# Arduino_MINI.net
KiCad netlist of a schematic drawn in Altium Designer
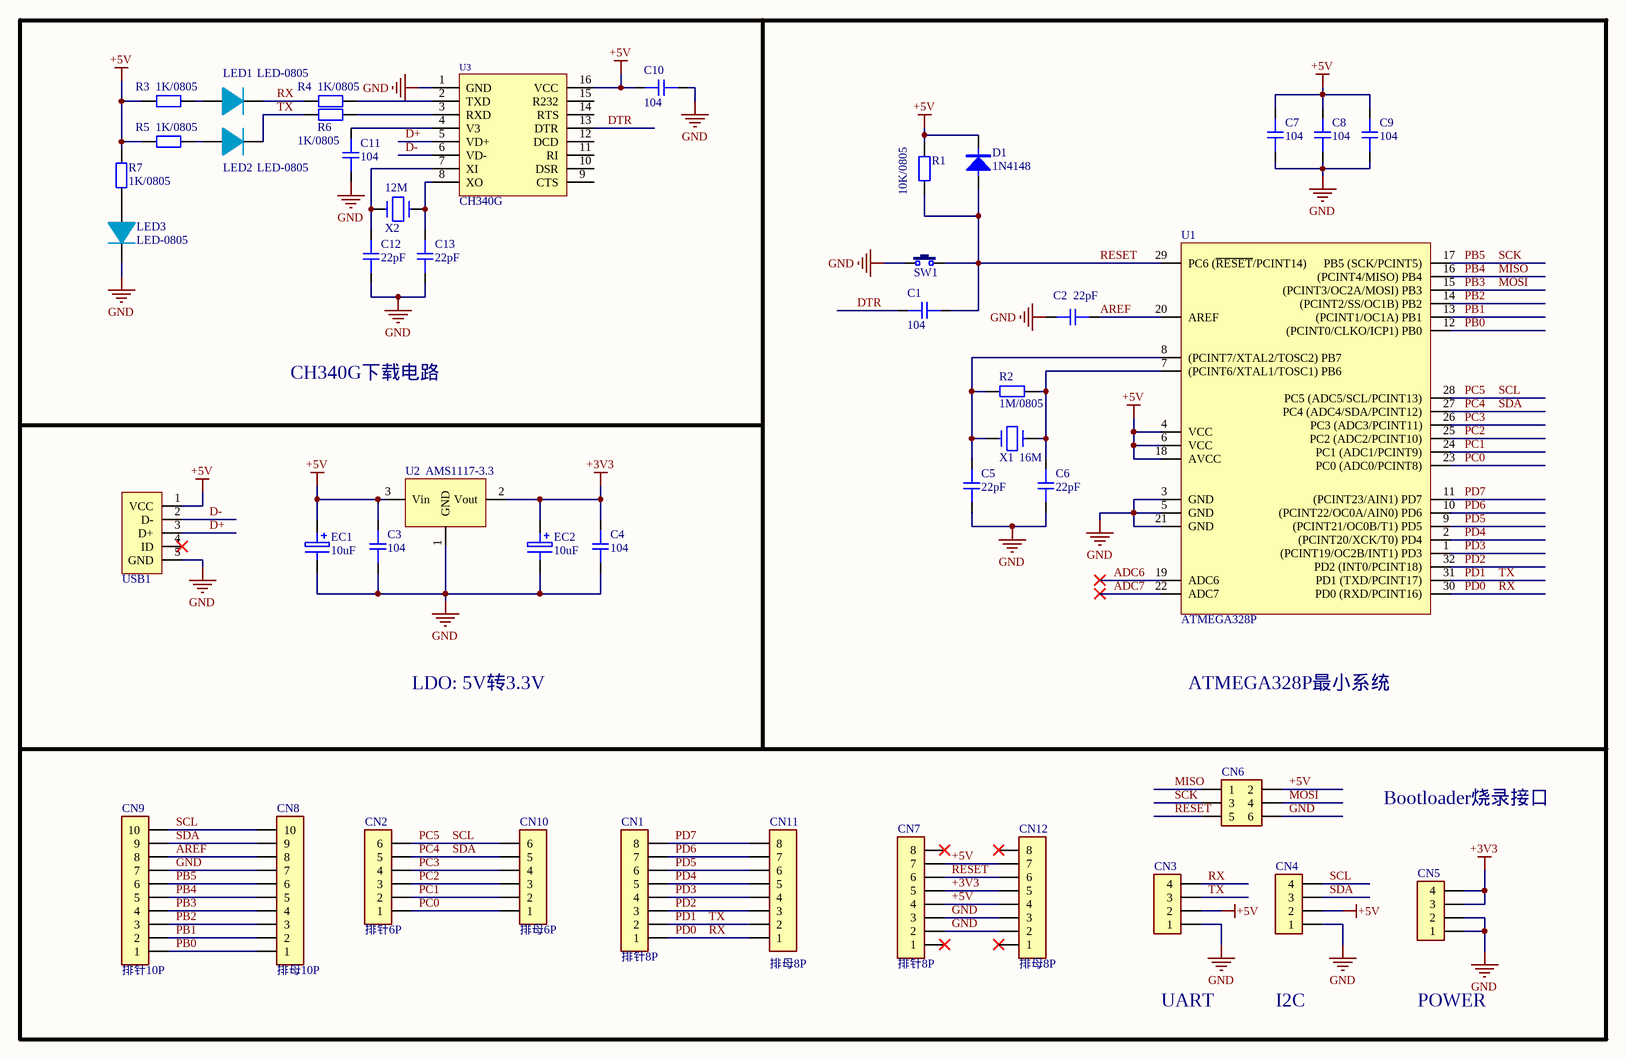
[diagram p0: Arduino开发板 MINI款.SchDoc]

(export (version "E")
  (design (tool "Eeschema 10.0.6"))
  (components
    (comp (ref "C1")
      (value "104")
      (footprint "C0805-SMT")
      (description "C")
      (libsource (lib "新-MZ-Library 2018-1-10") (part "C"))
    )
    (comp (ref "C2")
      (value "22pF")
      (footprint "C0805-SMT")
      (description "C")
      (libsource (lib "新-MZ-Library 2018-1-10") (part "C"))
    )
    (comp (ref "C3")
      (value "104")
      (footprint "C0805-SMT")
      (description "C")
      (libsource (lib "新-MZ-Library 2018-1-10") (part "C"))
    )
    (comp (ref "C4")
      (value "104")
      (footprint "C0805-SMT")
      (description "C")
      (libsource (lib "新-MZ-Library 2018-1-10") (part "C"))
    )
    (comp (ref "C5")
      (value "22pF")
      (footprint "C0805-SMT")
      (description "C")
      (libsource (lib "新-MZ-Library 2018-1-10") (part "C"))
    )
    (comp (ref "C6")
      (value "22pF")
      (footprint "C0805-SMT")
      (description "C")
      (libsource (lib "新-MZ-Library 2018-1-10") (part "C"))
    )
    (comp (ref "C7")
      (value "104")
      (footprint "C0805-SMT")
      (description "C")
      (libsource (lib "新-MZ-Library 2018-1-10") (part "C"))
    )
    (comp (ref "C8")
      (value "104")
      (footprint "C0805-SMT")
      (description "C")
      (libsource (lib "新-MZ-Library 2018-1-10") (part "C"))
    )
    (comp (ref "C9")
      (value "104")
      (footprint "C0805-SMT")
      (description "C")
      (libsource (lib "新-MZ-Library 2018-1-10") (part "C"))
    )
    (comp (ref "C10")
      (value "104")
      (footprint "C0805-SMT")
      (description "C")
      (libsource (lib "新-MZ-Library 2018-1-10") (part "C"))
    )
    (comp (ref "C11")
      (value "104")
      (footprint "C0805-SMT")
      (description "C")
      (libsource (lib "新-MZ-Library 2018-1-10") (part "C"))
    )
    (comp (ref "C12")
      (value "22pF")
      (footprint "C0805-SMT")
      (description "C")
      (libsource (lib "新-MZ-Library 2018-1-10") (part "C"))
    )
    (comp (ref "C13")
      (value "22pF")
      (footprint "C0805-SMT")
      (description "C")
      (libsource (lib "新-MZ-Library 2018-1-10") (part "C"))
    )
    (comp (ref "CN1")
      (value "排针8P")
      (footprint "sip8")
      (description "8P-SOCKET")
      (libsource (lib "") (part "CN8_1"))
    )
    (comp (ref "CN2")
      (value "排针6P")
      (footprint "sip6")
      (description "6P-SOCKET")
      (libsource (lib "") (part "CN6_1"))
    )
    (comp (ref "CN3")
      (value "CN4")
      (footprint "sip4")
      (description "4P-SOCKET")
      (libsource (lib "原理库MZ-Library 2021-2") (part "CN4"))
    )
    (comp (ref "CN4")
      (value "CN4")
      (footprint "sip4")
      (description "4P-SOCKET")
      (libsource (lib "原理库MZ-Library 2021-2") (part "CN4"))
    )
    (comp (ref "CN5")
      (value "CN4")
      (footprint "sip4")
      (description "4P-SOCKET")
      (libsource (lib "原理库MZ-Library 2021-2") (part "CN4"))
    )
    (comp (ref "CN6")
      (value "CN2*3")
      (footprint "sip2*3")
      (libsource (lib "原理库MZ-Library 2021-2") (part "CN2*3"))
    )
    (comp (ref "CN7")
      (value "排针8P")
      (footprint "SIP8")
      (description "8P-SOCKET")
      (libsource (lib "") (part "CN8_1"))
    )
    (comp (ref "CN8")
      (value "排母10P")
      (footprint "HDR2.54-M-LI-10P")
      (description "10P-SOCKET")
      (libsource (lib "原理库MZ-Library 2021-2") (part "CN10"))
    )
    (comp (ref "CN9")
      (value "排针10P")
      (footprint "SIP10")
      (description "10P-SOCKET")
      (libsource (lib "") (part "CN10_1"))
    )
    (comp (ref "CN10")
      (value "排母6P")
      (footprint "HDR2.54-M-LI-6P")
      (description "6P-SOCKET")
      (libsource (lib "原理库MZ-Library 2021-2") (part "CN6"))
    )
    (comp (ref "CN11")
      (value "排母8P")
      (footprint "HDR2.54-M-LI-8P")
      (description "8P-SOCKET")
      (libsource (lib "原理库MZ-Library 2021-2") (part "CN8"))
    )
    (comp (ref "CN12")
      (value "排母8P")
      (footprint "HDR2.54-M-LI-8P")
      (description "8P-SOCKET")
      (libsource (lib "原理库MZ-Library 2021-2") (part "CN8"))
    )
    (comp (ref "D1")
      (value "1N4148")
      (footprint "SOD123/F(4148)-SMT")
      (description "DIODE")
      (libsource (lib "新-MZ-Library 2018-1-10") (part "D"))
    )
    (comp (ref "EC1")
      (value "10uF")
      (footprint "CAE2.54-Φ5-AI")
      (description "EA")
      (libsource (lib "原理库MZ-Library 2021-2") (part "CAE"))
    )
    (comp (ref "EC2")
      (value "10uF")
      (footprint "CAE2.54-Φ5-AI")
      (description "EA")
      (libsource (lib "原理库MZ-Library 2021-2") (part "CAE"))
    )
    (comp (ref "LED1")
      (value "LED-0805")
      (footprint "LED 0805R")
      (description "LED_0805")
      (libsource (lib "常用元器件") (part "LED-0805"))
    )
    (comp (ref "LED2")
      (value "LED-0805")
      (footprint "LED 0805R")
      (description "LED_0805")
      (libsource (lib "常用元器件") (part "LED-0805"))
    )
    (comp (ref "LED3")
      (value "LED-0805")
      (footprint "LED 0805R")
      (description "LED_0805")
      (libsource (lib "常用元器件") (part "LED-0805"))
    )
    (comp (ref "R1")
      (value "10K/0805")
      (footprint "R0805-SMT")
      (description "RES")
      (libsource (lib "新-MZ-Library 2018-1-10") (part "R"))
    )
    (comp (ref "R2")
      (value "1M/0805")
      (footprint "R0805-SMT")
      (description "RES")
      (libsource (lib "新-MZ-Library 2018-1-10") (part "R"))
    )
    (comp (ref "R3")
      (value "1K/0805")
      (footprint "R0805-SMT")
      (description "RES")
      (libsource (lib "新-MZ-Library 2018-1-10") (part "R"))
    )
    (comp (ref "R4")
      (value "1K/0805")
      (footprint "R0805-SMT")
      (description "RES")
      (libsource (lib "新-MZ-Library 2018-1-10") (part "R"))
    )
    (comp (ref "R5")
      (value "1K/0805")
      (footprint "R0805-SMT")
      (description "RES")
      (libsource (lib "新-MZ-Library 2018-1-10") (part "R"))
    )
    (comp (ref "R6")
      (value "1K/0805")
      (footprint "R0805-SMT")
      (description "RES")
      (libsource (lib "新-MZ-Library 2018-1-10") (part "R"))
    )
    (comp (ref "R7")
      (value "1K/0805")
      (footprint "R0805-SMT")
      (description "RES")
      (libsource (lib "新-MZ-Library 2018-1-10") (part "R"))
    )
    (comp (ref "SW1")
      (value "6_6_5MM轻触按键")
      (footprint "TSW SMD-6*6*5")
      (libsource (lib "常用元器件") (part "6_6_5MM轻触按键"))
    )
    (comp (ref "U1")
      (value "ATMEGA328P")
      (footprint "LQFP32 7X7_M")
      (libsource (lib "常用元器件") (part "ATMEGA328P"))
    )
    (comp (ref "U2")
      (value "AMS1117-3.3")
      (footprint "SOT-223")
      (libsource (lib "常用元器件") (part "AMS1117-3.3"))
    )
    (comp (ref "U3")
      (value "CH340G")
      (footprint "IC-SOP16-1.27-SMT")
      (libsource (lib "原理库MZ-Library 2021-2") (part "CH340G"))
    )
    (comp (ref "USB1") (value "USB-5P") (footprint "USB-MICRO_D") (libsource (lib "常用元器件") (part "USB-5P")))
    (comp (ref "X1")
      (value "16M")
      (footprint "OSC HC-49S")
      (description "4M")
      (libsource (lib "原理库MZ-Library 2021-2") (part "X"))
    )
    (comp (ref "X2")
      (value "12M")
      (footprint "OSC HC-49S")
      (description "4M")
      (libsource (lib "原理库MZ-Library 2021-2") (part "X"))
    )
  )
  (nets
    (net (code "1") (name "+3V3") (class "Default")
      (node (ref "C4") (pin "2") (pinfunction "2_2") (pintype "passive"))
      (node (ref "CN12") (pin "5") (pinfunction "5_5") (pintype "passive"))
      (node (ref "CN5") (pin "3") (pinfunction "3_3") (pintype "passive"))
      (node (ref "CN5") (pin "4") (pinfunction "4_4") (pintype "passive"))
      (node (ref "CN7") (pin "5") (pinfunction "5_5") (pintype "passive"))
      (node (ref "EC2") (pin "1") (pinfunction "1_1") (pintype "passive"))
      (node (ref "U2") (pin "2") (pinfunction "Vout_2") (pintype "passive"))
    )
    (net (code "2") (name "+5V") (class "Default")
      (node (ref "C10") (pin "1") (pinfunction "1_1") (pintype "passive"))
      (node (ref "C3") (pin "2") (pinfunction "2_2") (pintype "passive"))
      (node (ref "C7") (pin "2") (pinfunction "2_2") (pintype "passive"))
      (node (ref "C8") (pin "2") (pinfunction "2_2") (pintype "passive"))
      (node (ref "C9") (pin "2") (pinfunction "2_2") (pintype "passive"))
      (node (ref "CN12") (pin "4") (pinfunction "4_4") (pintype "passive"))
      (node (ref "CN12") (pin "7") (pinfunction "7_7") (pintype "passive"))
      (node (ref "CN3") (pin "2") (pinfunction "2_2") (pintype "passive"))
      (node (ref "CN4") (pin "2") (pinfunction "2_2") (pintype "passive"))
      (node (ref "CN6") (pin "2") (pinfunction "2_2") (pintype "passive"))
      (node (ref "CN7") (pin "4") (pinfunction "4_4") (pintype "passive"))
      (node (ref "CN7") (pin "7") (pinfunction "7_7") (pintype "passive"))
      (node (ref "D1") (pin "K") (pinfunction "K_K") (pintype "passive"))
      (node (ref "EC1") (pin "1") (pinfunction "1_1") (pintype "passive"))
      (node (ref "R1") (pin "2") (pinfunction "2_2") (pintype "passive"))
      (node (ref "R3") (pin "1") (pinfunction "1_1") (pintype "passive"))
      (node (ref "R5") (pin "1") (pinfunction "1_1") (pintype "passive"))
      (node (ref "R7") (pin "2") (pinfunction "2_2") (pintype "passive"))
      (node (ref "U1") (pin "18") (pinfunction "AVCC_18") (pintype "passive"))
      (node (ref "U1") (pin "4") (pinfunction "VCC_4") (pintype "passive"))
      (node (ref "U1") (pin "6") (pinfunction "VCC_6") (pintype "passive"))
      (node (ref "U2") (pin "3") (pinfunction "Vin_3") (pintype "passive"))
      (node (ref "U3") (pin "16") (pinfunction "VCC_16") (pintype "passive"))
      (node (ref "USB1") (pin "1") (pinfunction "VCC_1") (pintype "passive"))
    )
    (net (code "3") (name "/ADC6") (class "Default")
      (node (ref "U1") (pin "19") (pinfunction "ADC6_19") (pintype "passive+no_connect"))
    )
    (net (code "4") (name "/ADC7") (class "Default")
      (node (ref "U1") (pin "22") (pinfunction "ADC7_22") (pintype "passive+no_connect"))
    )
    (net (code "5") (name "/AREF") (class "Default")
      (node (ref "C2") (pin "1") (pinfunction "1_1") (pintype "passive"))
      (node (ref "CN8") (pin "8") (pinfunction "8_8") (pintype "passive"))
      (node (ref "CN9") (pin "8") (pinfunction "8_8") (pintype "passive"))
      (node (ref "U1") (pin "20") (pinfunction "AREF_20") (pintype "passive"))
    )
    (net (code "6") (name "/D+") (class "Default")
      (node (ref "U3") (pin "5") (pinfunction "VD+_5") (pintype "passive"))
      (node (ref "USB1") (pin "3") (pinfunction "D+_3") (pintype "passive"))
    )
    (net (code "7") (name "/D-") (class "Default")
      (node (ref "U3") (pin "6") (pinfunction "VD-_6") (pintype "passive"))
      (node (ref "USB1") (pin "2") (pinfunction "D-_2") (pintype "passive"))
    )
    (net (code "8") (name "/DTR") (class "Default")
      (node (ref "C1") (pin "1") (pinfunction "1_1") (pintype "passive"))
      (node (ref "U3") (pin "13") (pinfunction "DTR_13") (pintype "passive"))
    )
    (net (code "9") (name "/MISO") (class "Default")
      (node (ref "CN6") (pin "1") (pinfunction "1_1") (pintype "passive"))
      (node (ref "CN8") (pin "5") (pinfunction "5_5") (pintype "passive"))
      (node (ref "CN9") (pin "5") (pinfunction "5_5") (pintype "passive"))
      (node (ref "U1") (pin "16") (pinfunction "(PCINT4/MISO)_PB4_16") (pintype "passive"))
    )
    (net (code "10") (name "/MOSI") (class "Default")
      (node (ref "CN6") (pin "4") (pinfunction "4_4") (pintype "passive"))
      (node (ref "CN8") (pin "4") (pinfunction "4_4") (pintype "passive"))
      (node (ref "CN9") (pin "4") (pinfunction "4_4") (pintype "passive"))
      (node (ref "U1") (pin "15") (pinfunction "(PCINT3/OC2A/MOSI)_PB3_15") (pintype "passive"))
    )
    (net (code "11") (name "/PB0") (class "Default")
      (node (ref "CN8") (pin "1") (pinfunction "1_1") (pintype "passive"))
      (node (ref "CN9") (pin "1") (pinfunction "1_1") (pintype "passive"))
      (node (ref "U1") (pin "12") (pinfunction "(PCINT0/CLKO/ICP1)_PB0_12") (pintype "passive"))
    )
    (net (code "12") (name "/PB1") (class "Default")
      (node (ref "CN8") (pin "2") (pinfunction "2_2") (pintype "passive"))
      (node (ref "CN9") (pin "2") (pinfunction "2_2") (pintype "passive"))
      (node (ref "U1") (pin "13") (pinfunction "(PCINT1/OC1A)_PB1_13") (pintype "passive"))
    )
    (net (code "13") (name "/PB2") (class "Default")
      (node (ref "CN8") (pin "3") (pinfunction "3_3") (pintype "passive"))
      (node (ref "CN9") (pin "3") (pinfunction "3_3") (pintype "passive"))
      (node (ref "U1") (pin "14") (pinfunction "(PCINT2/SS/OC1B)_PB2_14") (pintype "passive"))
    )
    (net (code "14") (name "/PB5") (class "Default")
      (node (ref "CN6") (pin "3") (pinfunction "3_3") (pintype "passive"))
      (node (ref "CN8") (pin "6") (pinfunction "6_6") (pintype "passive"))
      (node (ref "CN9") (pin "6") (pinfunction "6_6") (pintype "passive"))
      (node (ref "U1") (pin "17") (pinfunction "PB5_(SCK/PCINT5)_17") (pintype "passive"))
    )
    (net (code "15") (name "/PC0") (class "Default")
      (node (ref "CN10") (pin "1") (pinfunction "1_1") (pintype "passive"))
      (node (ref "CN2") (pin "1") (pinfunction "1_1") (pintype "passive"))
      (node (ref "U1") (pin "23") (pinfunction "PC0_(ADC0/PCINT8)_23") (pintype "passive"))
    )
    (net (code "16") (name "/PC1") (class "Default")
      (node (ref "CN10") (pin "2") (pinfunction "2_2") (pintype "passive"))
      (node (ref "CN2") (pin "2") (pinfunction "2_2") (pintype "passive"))
      (node (ref "U1") (pin "24") (pinfunction "PC1_(ADC1/PCINT9)_24") (pintype "passive"))
    )
    (net (code "17") (name "/PC2") (class "Default")
      (node (ref "CN10") (pin "3") (pinfunction "3_3") (pintype "passive"))
      (node (ref "CN2") (pin "3") (pinfunction "3_3") (pintype "passive"))
      (node (ref "U1") (pin "25") (pinfunction "PC2_(ADC2/PCINT10)_25") (pintype "passive"))
    )
    (net (code "18") (name "/PC3") (class "Default")
      (node (ref "CN10") (pin "4") (pinfunction "4_4") (pintype "passive"))
      (node (ref "CN2") (pin "4") (pinfunction "4_4") (pintype "passive"))
      (node (ref "U1") (pin "26") (pinfunction "PC3_(ADC3/PCINT11)_26") (pintype "passive"))
    )
    (net (code "19") (name "/PC4") (class "Default")
      (node (ref "CN10") (pin "5") (pinfunction "5_5") (pintype "passive"))
      (node (ref "CN2") (pin "5") (pinfunction "5_5") (pintype "passive"))
      (node (ref "CN4") (pin "3") (pinfunction "3_3") (pintype "passive"))
      (node (ref "CN8") (pin "9") (pinfunction "9_9") (pintype "passive"))
      (node (ref "CN9") (pin "9") (pinfunction "9_9") (pintype "passive"))
      (node (ref "U1") (pin "27") (pinfunction "PC4_(ADC4/SDA/PCINT12)_27") (pintype "passive"))
    )
    (net (code "20") (name "/PC5") (class "Default")
      (node (ref "CN10") (pin "6") (pinfunction "6_6") (pintype "passive"))
      (node (ref "CN2") (pin "6") (pinfunction "6_6") (pintype "passive"))
      (node (ref "CN4") (pin "4") (pinfunction "4_4") (pintype "passive"))
      (node (ref "CN8") (pin "10") (pinfunction "10_10") (pintype "passive"))
      (node (ref "CN9") (pin "10") (pinfunction "10_10") (pintype "passive"))
      (node (ref "U1") (pin "28") (pinfunction "PC5_(ADC5/SCL/PCINT13)_28") (pintype "passive"))
    )
    (net (code "21") (name "/PD0") (class "Default")
      (node (ref "CN1") (pin "1") (pinfunction "1_1") (pintype "passive"))
      (node (ref "CN11") (pin "1") (pinfunction "1_1") (pintype "passive"))
      (node (ref "CN3") (pin "4") (pinfunction "4_4") (pintype "passive"))
      (node (ref "LED1") (pin "1") (pinfunction "1_1") (pintype "passive"))
      (node (ref "R4") (pin "1") (pinfunction "1_1") (pintype "passive"))
      (node (ref "U1") (pin "30") (pinfunction "PD0_(RXD/PCINT16)_30") (pintype "passive"))
    )
    (net (code "22") (name "/PD1") (class "Default")
      (node (ref "CN1") (pin "2") (pinfunction "2_2") (pintype "passive"))
      (node (ref "CN11") (pin "2") (pinfunction "2_2") (pintype "passive"))
      (node (ref "CN3") (pin "3") (pinfunction "3_3") (pintype "passive"))
      (node (ref "LED2") (pin "1") (pinfunction "1_1") (pintype "passive"))
      (node (ref "R6") (pin "1") (pinfunction "1_1") (pintype "passive"))
      (node (ref "U1") (pin "31") (pinfunction "PD1_(TXD/PCINT17)_31") (pintype "passive"))
    )
    (net (code "23") (name "/PD2") (class "Default")
      (node (ref "CN1") (pin "3") (pinfunction "3_3") (pintype "passive"))
      (node (ref "CN11") (pin "3") (pinfunction "3_3") (pintype "passive"))
      (node (ref "U1") (pin "32") (pinfunction "PD2_(INT0/PCINT18)_32") (pintype "passive"))
    )
    (net (code "24") (name "/PD3") (class "Default")
      (node (ref "CN1") (pin "4") (pinfunction "4_4") (pintype "passive"))
      (node (ref "CN11") (pin "4") (pinfunction "4_4") (pintype "passive"))
      (node (ref "U1") (pin "1") (pinfunction "(PCINT19/OC2B/INT1)_PD3_1") (pintype "passive"))
    )
    (net (code "25") (name "/PD4") (class "Default")
      (node (ref "CN1") (pin "5") (pinfunction "5_5") (pintype "passive"))
      (node (ref "CN11") (pin "5") (pinfunction "5_5") (pintype "passive"))
      (node (ref "U1") (pin "2") (pinfunction "(PCINT20/XCK/T0)_PD4_2") (pintype "passive"))
    )
    (net (code "26") (name "/PD5") (class "Default")
      (node (ref "CN1") (pin "6") (pinfunction "6_6") (pintype "passive"))
      (node (ref "CN11") (pin "6") (pinfunction "6_6") (pintype "passive"))
      (node (ref "U1") (pin "9") (pinfunction "(PCINT21/OC0B/T1)_PD5_9") (pintype "passive"))
    )
    (net (code "27") (name "/PD6") (class "Default")
      (node (ref "CN1") (pin "7") (pinfunction "7_7") (pintype "passive"))
      (node (ref "CN11") (pin "7") (pinfunction "7_7") (pintype "passive"))
      (node (ref "U1") (pin "10") (pinfunction "(PCINT22/OC0A/AIN0)_PD6_10") (pintype "passive"))
    )
    (net (code "28") (name "/PD7") (class "Default")
      (node (ref "CN1") (pin "8") (pinfunction "8_8") (pintype "passive"))
      (node (ref "CN11") (pin "8") (pinfunction "8_8") (pintype "passive"))
      (node (ref "U1") (pin "11") (pinfunction "(PCINT23/AIN1)_PD7_11") (pintype "passive"))
    )
    (net (code "29") (name "/RESET") (class "Default")
      (node (ref "C1") (pin "2") (pinfunction "2_2") (pintype "passive"))
      (node (ref "CN12") (pin "6") (pinfunction "6_6") (pintype "passive"))
      (node (ref "CN6") (pin "5") (pinfunction "5_5") (pintype "passive"))
      (node (ref "CN7") (pin "6") (pinfunction "6_6") (pintype "passive"))
      (node (ref "D1") (pin "A") (pinfunction "A_A") (pintype "passive"))
      (node (ref "R1") (pin "1") (pinfunction "1_1") (pintype "passive"))
      (node (ref "SW1") (pin "3") (pinfunction "3_3") (pintype "passive"))
      (node (ref "U1") (pin "29") (pinfunction "PC6_(~{RESET}/PCINT14)_29") (pintype "passive"))
    )
    (net (code "30") (name "GND") (class "Default")
      (node (ref "C10") (pin "2") (pinfunction "2_2") (pintype "passive"))
      (node (ref "C11") (pin "1") (pinfunction "1_1") (pintype "passive"))
      (node (ref "C12") (pin "1") (pinfunction "1_1") (pintype "passive"))
      (node (ref "C13") (pin "1") (pinfunction "1_1") (pintype "passive"))
      (node (ref "C2") (pin "2") (pinfunction "2_2") (pintype "passive"))
      (node (ref "C3") (pin "1") (pinfunction "1_1") (pintype "passive"))
      (node (ref "C4") (pin "1") (pinfunction "1_1") (pintype "passive"))
      (node (ref "C5") (pin "1") (pinfunction "1_1") (pintype "passive"))
      (node (ref "C6") (pin "1") (pinfunction "1_1") (pintype "passive"))
      (node (ref "C7") (pin "1") (pinfunction "1_1") (pintype "passive"))
      (node (ref "C8") (pin "1") (pinfunction "1_1") (pintype "passive"))
      (node (ref "C9") (pin "1") (pinfunction "1_1") (pintype "passive"))
      (node (ref "CN12") (pin "2") (pinfunction "2_2") (pintype "passive"))
      (node (ref "CN12") (pin "3") (pinfunction "3_3") (pintype "passive"))
      (node (ref "CN3") (pin "1") (pinfunction "1_1") (pintype "passive"))
      (node (ref "CN4") (pin "1") (pinfunction "1_1") (pintype "passive"))
      (node (ref "CN5") (pin "1") (pinfunction "1_1") (pintype "passive"))
      (node (ref "CN5") (pin "2") (pinfunction "2_2") (pintype "passive"))
      (node (ref "CN6") (pin "6") (pinfunction "6_6") (pintype "passive"))
      (node (ref "CN7") (pin "2") (pinfunction "2_2") (pintype "passive"))
      (node (ref "CN7") (pin "3") (pinfunction "3_3") (pintype "passive"))
      (node (ref "CN8") (pin "7") (pinfunction "7_7") (pintype "passive"))
      (node (ref "CN9") (pin "7") (pinfunction "7_7") (pintype "passive"))
      (node (ref "EC1") (pin "2") (pinfunction "2_2") (pintype "passive"))
      (node (ref "EC2") (pin "2") (pinfunction "2_2") (pintype "passive"))
      (node (ref "LED3") (pin "1") (pinfunction "1_1") (pintype "passive"))
      (node (ref "SW1") (pin "1") (pinfunction "1_1") (pintype "passive"))
      (node (ref "U1") (pin "21") (pinfunction "GND_21") (pintype "passive"))
      (node (ref "U1") (pin "3") (pinfunction "GND_3") (pintype "passive"))
      (node (ref "U1") (pin "5") (pinfunction "GND_5") (pintype "passive"))
      (node (ref "U2") (pin "1") (pinfunction "GND_1") (pintype "passive"))
      (node (ref "U3") (pin "1") (pinfunction "GND_1") (pintype "passive"))
      (node (ref "USB1") (pin "5") (pinfunction "GND_5") (pintype "passive"))
    )
    (net (code "31") (name "Net-(LED1-Pad2)") (class "Default")
      (node (ref "LED1") (pin "2") (pinfunction "2_2") (pintype "passive"))
      (node (ref "R3") (pin "2") (pinfunction "2_2") (pintype "passive"))
    )
    (net (code "32") (name "Net-(LED2-Pad2)") (class "Default")
      (node (ref "LED2") (pin "2") (pinfunction "2_2") (pintype "passive"))
      (node (ref "R5") (pin "2") (pinfunction "2_2") (pintype "passive"))
    )
    (net (code "33") (name "Net-(LED3-Pad2)") (class "Default")
      (node (ref "LED3") (pin "2") (pinfunction "2_2") (pintype "passive"))
      (node (ref "R7") (pin "1") (pinfunction "1_1") (pintype "passive"))
    )
    (net (code "34") (name "Net-(U1-(PCINT6{slash}XTAL1{slash}TOSC1)_PB6)") (class "Default")
      (node (ref "C6") (pin "2") (pinfunction "2_2") (pintype "passive"))
      (node (ref "R2") (pin "1") (pinfunction "1_1") (pintype "passive"))
      (node (ref "U1") (pin "7") (pinfunction "(PCINT6/XTAL1/TOSC1)_PB6_7") (pintype "passive"))
      (node (ref "X1") (pin "2") (pinfunction "2_2") (pintype "passive"))
    )
    (net (code "35") (name "Net-(U1-(PCINT7{slash}XTAL2{slash}TOSC2)_PB7)") (class "Default")
      (node (ref "C5") (pin "2") (pinfunction "2_2") (pintype "passive"))
      (node (ref "R2") (pin "2") (pinfunction "2_2") (pintype "passive"))
      (node (ref "U1") (pin "8") (pinfunction "(PCINT7/XTAL2/TOSC2)_PB7_8") (pintype "passive"))
      (node (ref "X1") (pin "1") (pinfunction "1_1") (pintype "passive"))
    )
    (net (code "36") (name "Net-(U3-RXD)") (class "Default")
      (node (ref "R6") (pin "2") (pinfunction "2_2") (pintype "passive"))
      (node (ref "U3") (pin "3") (pinfunction "RXD_3") (pintype "passive"))
    )
    (net (code "37") (name "Net-(U3-TXD)") (class "Default")
      (node (ref "R4") (pin "2") (pinfunction "2_2") (pintype "passive"))
      (node (ref "U3") (pin "2") (pinfunction "TXD_2") (pintype "passive"))
    )
    (net (code "38") (name "Net-(U3-V3)") (class "Default")
      (node (ref "C11") (pin "2") (pinfunction "2_2") (pintype "passive"))
      (node (ref "U3") (pin "4") (pinfunction "V3_4") (pintype "passive"))
    )
    (net (code "39") (name "Net-(U3-XI)") (class "Default")
      (node (ref "C12") (pin "2") (pinfunction "2_2") (pintype "passive"))
      (node (ref "U3") (pin "7") (pinfunction "XI_7") (pintype "passive"))
      (node (ref "X2") (pin "1") (pinfunction "1_1") (pintype "passive"))
    )
    (net (code "40") (name "Net-(U3-XO)") (class "Default")
      (node (ref "C13") (pin "2") (pinfunction "2_2") (pintype "passive"))
      (node (ref "U3") (pin "8") (pinfunction "XO_8") (pintype "passive"))
      (node (ref "X2") (pin "2") (pinfunction "2_2") (pintype "passive"))
    )
    (net (code "41") (name "unconnected-(CN7-Pad1)") (class "Default")
      (node (ref "CN7") (pin "1") (pinfunction "1_1") (pintype "passive+no_connect"))
    )
    (net (code "42") (name "unconnected-(CN7-Pad8)") (class "Default")
      (node (ref "CN7") (pin "8") (pinfunction "8_8") (pintype "passive+no_connect"))
    )
    (net (code "43") (name "unconnected-(CN12-Pad1)") (class "Default")
      (node (ref "CN12") (pin "1") (pinfunction "1_1") (pintype "passive+no_connect"))
    )
    (net (code "44") (name "unconnected-(CN12-Pad8)") (class "Default")
      (node (ref "CN12") (pin "8") (pinfunction "8_8") (pintype "passive+no_connect"))
    )
    (net (code "45") (name "unconnected-(U3-CTS-Pad9)") (class "Default")
      (node (ref "U3") (pin "9") (pinfunction "CTS_9") (pintype "passive"))
    )
    (net (code "46") (name "unconnected-(U3-DCD-Pad12)") (class "Default")
      (node (ref "U3") (pin "12") (pinfunction "DCD_12") (pintype "passive"))
    )
    (net (code "47") (name "unconnected-(U3-DSR-Pad10)") (class "Default")
      (node (ref "U3") (pin "10") (pinfunction "DSR_10") (pintype "passive"))
    )
    (net (code "48") (name "unconnected-(U3-R232-Pad15)") (class "Default")
      (node (ref "U3") (pin "15") (pinfunction "R232_15") (pintype "passive"))
    )
    (net (code "49") (name "unconnected-(U3-RI-Pad11)") (class "Default")
      (node (ref "U3") (pin "11") (pinfunction "RI_11") (pintype "passive"))
    )
    (net (code "50") (name "unconnected-(U3-RTS-Pad14)") (class "Default")
      (node (ref "U3") (pin "14") (pinfunction "RTS_14") (pintype "passive"))
    )
    (net (code "51") (name "unconnected-(USB1-ID-Pad4)") (class "Default")
      (node (ref "USB1") (pin "4") (pinfunction "ID_4") (pintype "passive+no_connect"))
    )
  )
)
